# Bipolar_Matrix_Mixer_4x2.net
KiCad netlist of a schematic drawn in EAGLE
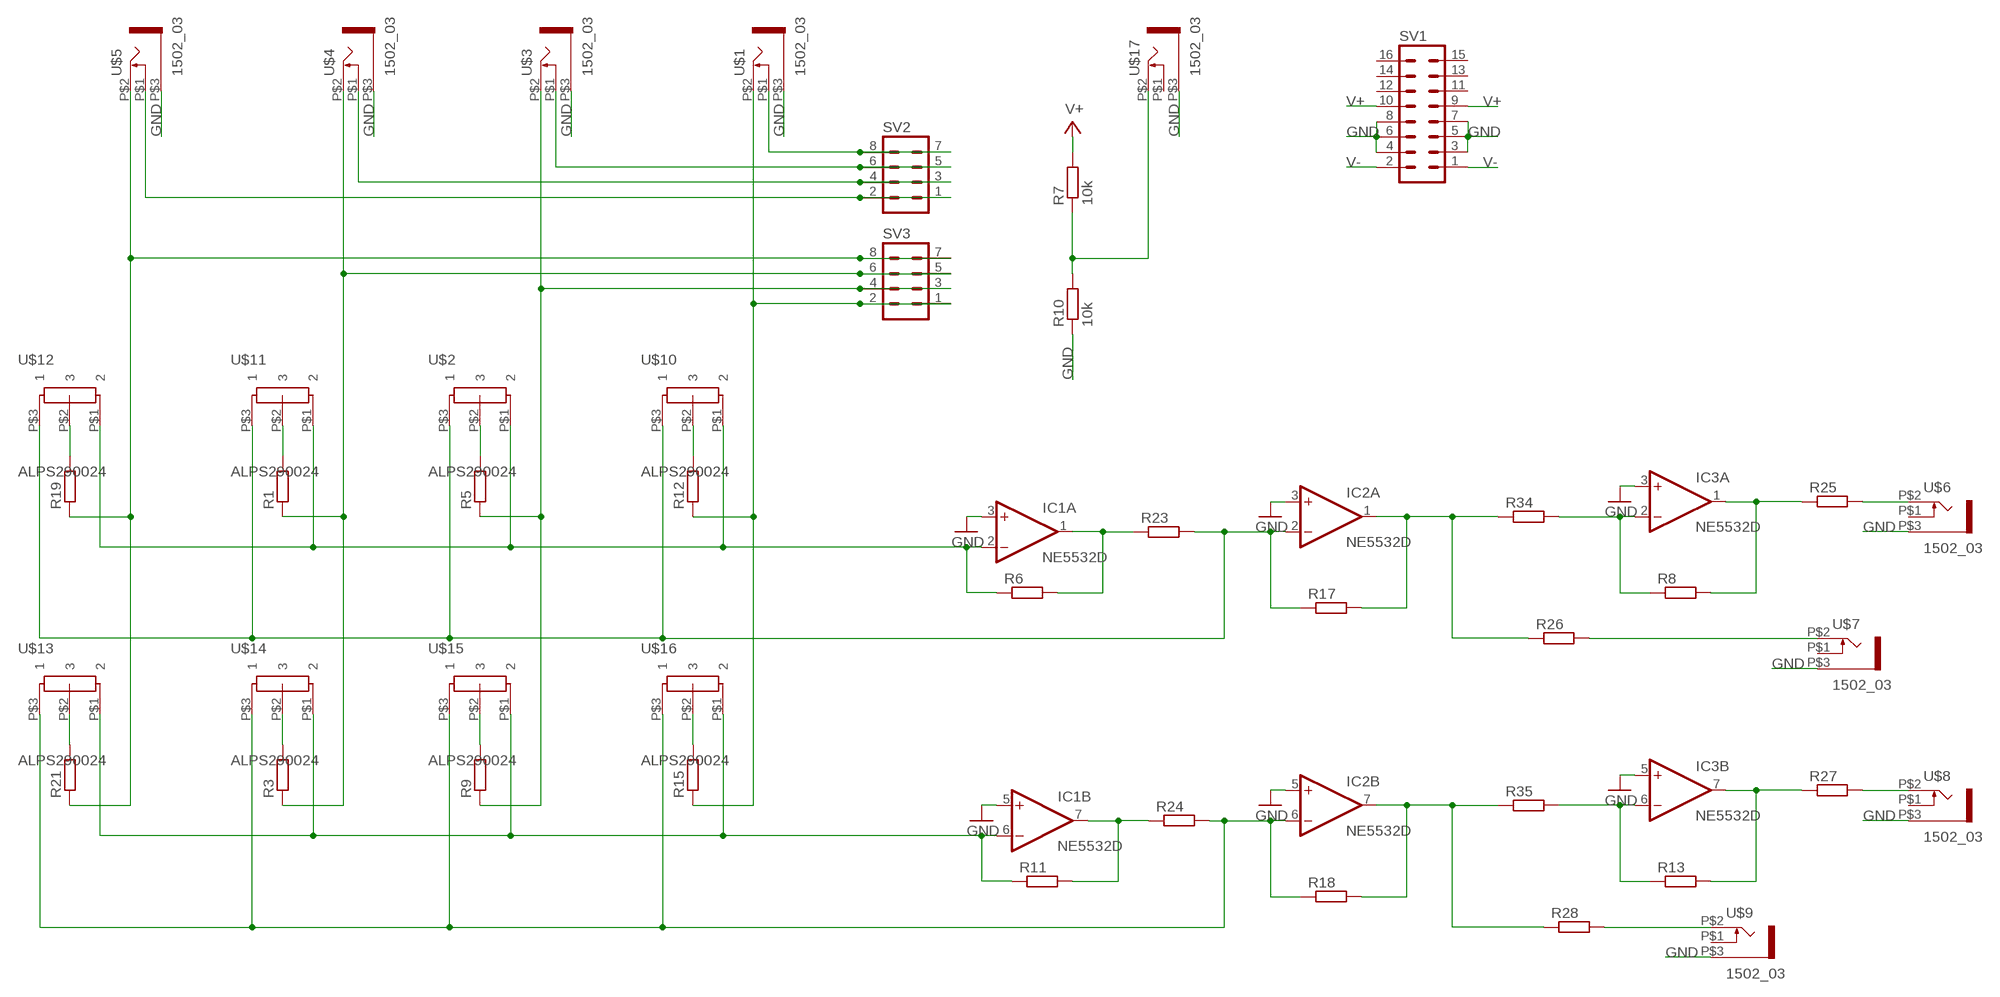
[diagram p0: schematic, sheet 1]

(export (version "E")
  (design (tool "Eeschema 10.0.6"))
  (components
    (comp (ref "IC1")
      (value "NE5532D")
      (footprint "eagle-import:SO08")
      (libsource (lib "eagle-import") (part "NE5532D"))
    )
    (comp (ref "IC2")
      (value "NE5532D")
      (footprint "eagle-import:SO08")
      (libsource (lib "eagle-import") (part "NE5532D"))
    )
    (comp (ref "IC3")
      (value "NE5532D")
      (footprint "eagle-import:SO08")
      (libsource (lib "eagle-import") (part "NE5532D"))
    )
    (comp (ref "R1")
      (value "R-EU_R0603")
      (footprint "eagle-import:R0603")
      (libsource (lib "eagle-import") (part "R-EU_R0603"))
    )
    (comp (ref "R3")
      (value "R-EU_R0603")
      (footprint "eagle-import:R0603")
      (libsource (lib "eagle-import") (part "R-EU_R0603"))
    )
    (comp (ref "R5")
      (value "R-EU_R0603")
      (footprint "eagle-import:R0603")
      (libsource (lib "eagle-import") (part "R-EU_R0603"))
    )
    (comp (ref "R6")
      (value "R-EU_R0603")
      (footprint "eagle-import:R0603")
      (libsource (lib "eagle-import") (part "R-EU_R0603"))
    )
    (comp (ref "R7")
      (value "10k")
      (footprint "eagle-import:R0603")
      (libsource (lib "eagle-import") (part "R-EU_R0603"))
    )
    (comp (ref "R8")
      (value "R-EU_R0603")
      (footprint "eagle-import:R0603")
      (libsource (lib "eagle-import") (part "R-EU_R0603"))
    )
    (comp (ref "R9")
      (value "R-EU_R0603")
      (footprint "eagle-import:R0603")
      (libsource (lib "eagle-import") (part "R-EU_R0603"))
    )
    (comp (ref "R10")
      (value "10k")
      (footprint "eagle-import:R0603")
      (libsource (lib "eagle-import") (part "R-EU_R0603"))
    )
    (comp (ref "R11")
      (value "R-EU_R0603")
      (footprint "eagle-import:R0603")
      (libsource (lib "eagle-import") (part "R-EU_R0603"))
    )
    (comp (ref "R12")
      (value "R-EU_R0603")
      (footprint "eagle-import:R0603")
      (libsource (lib "eagle-import") (part "R-EU_R0603"))
    )
    (comp (ref "R13")
      (value "R-EU_R0603")
      (footprint "eagle-import:R0603")
      (libsource (lib "eagle-import") (part "R-EU_R0603"))
    )
    (comp (ref "R15")
      (value "R-EU_R0603")
      (footprint "eagle-import:R0603")
      (libsource (lib "eagle-import") (part "R-EU_R0603"))
    )
    (comp (ref "R17")
      (value "R-EU_R0603")
      (footprint "eagle-import:R0603")
      (libsource (lib "eagle-import") (part "R-EU_R0603"))
    )
    (comp (ref "R18")
      (value "R-EU_R0603")
      (footprint "eagle-import:R0603")
      (libsource (lib "eagle-import") (part "R-EU_R0603"))
    )
    (comp (ref "R19")
      (value "R-EU_R0603")
      (footprint "eagle-import:R0603")
      (libsource (lib "eagle-import") (part "R-EU_R0603"))
    )
    (comp (ref "R21")
      (value "R-EU_R0603")
      (footprint "eagle-import:R0603")
      (libsource (lib "eagle-import") (part "R-EU_R0603"))
    )
    (comp (ref "R23")
      (value "R-EU_R0603")
      (footprint "eagle-import:R0603")
      (libsource (lib "eagle-import") (part "R-EU_R0603"))
    )
    (comp (ref "R24")
      (value "R-EU_R0603")
      (footprint "eagle-import:R0603")
      (libsource (lib "eagle-import") (part "R-EU_R0603"))
    )
    (comp (ref "R25")
      (value "R-EU_R0603")
      (footprint "eagle-import:R0603")
      (libsource (lib "eagle-import") (part "R-EU_R0603"))
    )
    (comp (ref "R26")
      (value "R-EU_R0603")
      (footprint "eagle-import:R0603")
      (libsource (lib "eagle-import") (part "R-EU_R0603"))
    )
    (comp (ref "R27")
      (value "R-EU_R0603")
      (footprint "eagle-import:R0603")
      (libsource (lib "eagle-import") (part "R-EU_R0603"))
    )
    (comp (ref "R28")
      (value "R-EU_R0603")
      (footprint "eagle-import:R0603")
      (libsource (lib "eagle-import") (part "R-EU_R0603"))
    )
    (comp (ref "R34")
      (value "R-EU_R0603")
      (footprint "eagle-import:R0603")
      (libsource (lib "eagle-import") (part "R-EU_R0603"))
    )
    (comp (ref "R35")
      (value "R-EU_R0603")
      (footprint "eagle-import:R0603")
      (libsource (lib "eagle-import") (part "R-EU_R0603"))
    )
    (comp (ref "SV1")
      (value "MA08-2")
      (footprint "eagle-import:MA08-2")
      (libsource (lib "eagle-import") (part "MA08-2"))
    )
    (comp (ref "SV2")
      (value "MA04-2")
      (footprint "eagle-import:MA04-2")
      (libsource (lib "eagle-import") (part "MA04-2"))
    )
    (comp (ref "SV3")
      (value "MA04-2")
      (footprint "eagle-import:MA04-2")
      (libsource (lib "eagle-import") (part "MA04-2"))
    )
    (comp (ref "U$1")
      (value "1502_03")
      (footprint "eagle-import:1502_03")
      (libsource (lib "eagle-import") (part "1502_03"))
    )
    (comp (ref "U$2")
      (value "ALPS290024")
      (footprint "eagle-import:POT")
      (libsource (lib "eagle-import") (part "ALPS290024"))
    )
    (comp (ref "U$3")
      (value "1502_03")
      (footprint "eagle-import:1502_03")
      (libsource (lib "eagle-import") (part "1502_03"))
    )
    (comp (ref "U$4")
      (value "1502_03")
      (footprint "eagle-import:1502_03")
      (libsource (lib "eagle-import") (part "1502_03"))
    )
    (comp (ref "U$5")
      (value "1502_03")
      (footprint "eagle-import:1502_03")
      (libsource (lib "eagle-import") (part "1502_03"))
    )
    (comp (ref "U$6")
      (value "1502_03")
      (footprint "eagle-import:1502_03")
      (libsource (lib "eagle-import") (part "1502_03"))
    )
    (comp (ref "U$7")
      (value "1502_03")
      (footprint "eagle-import:1502_03")
      (libsource (lib "eagle-import") (part "1502_03"))
    )
    (comp (ref "U$8")
      (value "1502_03")
      (footprint "eagle-import:1502_03")
      (libsource (lib "eagle-import") (part "1502_03"))
    )
    (comp (ref "U$9")
      (value "1502_03")
      (footprint "eagle-import:1502_03")
      (libsource (lib "eagle-import") (part "1502_03"))
    )
    (comp (ref "U$10")
      (value "ALPS290024")
      (footprint "eagle-import:POT")
      (libsource (lib "eagle-import") (part "ALPS290024"))
    )
    (comp (ref "U$11")
      (value "ALPS290024")
      (footprint "eagle-import:POT")
      (libsource (lib "eagle-import") (part "ALPS290024"))
    )
    (comp (ref "U$12")
      (value "ALPS290024")
      (footprint "eagle-import:POT")
      (libsource (lib "eagle-import") (part "ALPS290024"))
    )
    (comp (ref "U$13")
      (value "ALPS290024")
      (footprint "eagle-import:POT")
      (libsource (lib "eagle-import") (part "ALPS290024"))
    )
    (comp (ref "U$14")
      (value "ALPS290024")
      (footprint "eagle-import:POT")
      (libsource (lib "eagle-import") (part "ALPS290024"))
    )
    (comp (ref "U$15")
      (value "ALPS290024")
      (footprint "eagle-import:POT")
      (libsource (lib "eagle-import") (part "ALPS290024"))
    )
    (comp (ref "U$16")
      (value "ALPS290024")
      (footprint "eagle-import:POT")
      (libsource (lib "eagle-import") (part "ALPS290024"))
    )
    (comp (ref "U$17")
      (value "1502_03")
      (footprint "eagle-import:1502_03")
      (libsource (lib "eagle-import") (part "1502_03"))
    )
  )
  (nets
    (net (code "1") (name "/V-") (class "Default")
      (node (ref "SV1") (pin "1") (pinfunction "1_1") (pintype "passive"))
      (node (ref "SV1") (pin "2") (pinfunction "2_2") (pintype "passive"))
    )
    (net (code "2") (name "GND") (class "Default")
      (node (ref "IC1") (pin "3") (pinfunction "+IN_3") (pintype "input"))
      (node (ref "IC1") (pin "5") (pinfunction "+IN_5") (pintype "input"))
      (node (ref "IC2") (pin "3") (pinfunction "+IN_3") (pintype "input"))
      (node (ref "IC2") (pin "5") (pinfunction "+IN_5") (pintype "input"))
      (node (ref "IC3") (pin "3") (pinfunction "+IN_3") (pintype "input"))
      (node (ref "IC3") (pin "5") (pinfunction "+IN_5") (pintype "input"))
      (node (ref "R10") (pin "1") (pinfunction "1_1") (pintype "passive"))
      (node (ref "SV1") (pin "3") (pinfunction "3_3") (pintype "passive"))
      (node (ref "SV1") (pin "4") (pinfunction "4_4") (pintype "passive"))
      (node (ref "SV1") (pin "5") (pinfunction "5_5") (pintype "passive"))
      (node (ref "SV1") (pin "6") (pinfunction "6_6") (pintype "passive"))
      (node (ref "SV1") (pin "7") (pinfunction "7_7") (pintype "passive"))
      (node (ref "SV1") (pin "8") (pinfunction "8_8") (pintype "passive"))
      (node (ref "U$1") (pin "P$3") (pinfunction "5_P$3") (pintype "passive"))
      (node (ref "U$17") (pin "P$3") (pinfunction "5_P$3") (pintype "passive"))
      (node (ref "U$3") (pin "P$3") (pinfunction "5_P$3") (pintype "passive"))
      (node (ref "U$4") (pin "P$3") (pinfunction "5_P$3") (pintype "passive"))
      (node (ref "U$5") (pin "P$3") (pinfunction "5_P$3") (pintype "passive"))
      (node (ref "U$6") (pin "P$3") (pinfunction "5_P$3") (pintype "passive"))
      (node (ref "U$7") (pin "P$3") (pinfunction "5_P$3") (pintype "passive"))
      (node (ref "U$8") (pin "P$3") (pinfunction "5_P$3") (pintype "passive"))
      (node (ref "U$9") (pin "P$3") (pinfunction "5_P$3") (pintype "passive"))
    )
    (net (code "3") (name "Net-(IC1A--IN)") (class "Default")
      (node (ref "IC1") (pin "2") (pinfunction "-IN_2") (pintype "input"))
      (node (ref "R6") (pin "1") (pinfunction "1_1") (pintype "passive"))
      (node (ref "U$10") (pin "P$1") (pinfunction "2_P$1") (pintype "bidirectional"))
      (node (ref "U$11") (pin "P$1") (pinfunction "2_P$1") (pintype "bidirectional"))
      (node (ref "U$12") (pin "P$1") (pinfunction "2_P$1") (pintype "bidirectional"))
      (node (ref "U$2") (pin "P$1") (pinfunction "2_P$1") (pintype "bidirectional"))
    )
    (net (code "4") (name "Net-(IC1A-OUT)") (class "Default")
      (node (ref "IC1") (pin "1") (pinfunction "OUT_1") (pintype "output"))
      (node (ref "R23") (pin "1") (pinfunction "1_1") (pintype "passive"))
      (node (ref "R6") (pin "2") (pinfunction "2_2") (pintype "passive"))
    )
    (net (code "5") (name "Net-(IC1B--IN)") (class "Default")
      (node (ref "IC1") (pin "6") (pinfunction "-IN_6") (pintype "input"))
      (node (ref "R11") (pin "1") (pinfunction "1_1") (pintype "passive"))
      (node (ref "U$13") (pin "P$1") (pinfunction "2_P$1") (pintype "bidirectional"))
      (node (ref "U$14") (pin "P$1") (pinfunction "2_P$1") (pintype "bidirectional"))
      (node (ref "U$15") (pin "P$1") (pinfunction "2_P$1") (pintype "bidirectional"))
      (node (ref "U$16") (pin "P$1") (pinfunction "2_P$1") (pintype "bidirectional"))
    )
    (net (code "6") (name "Net-(IC1B-OUT)") (class "Default")
      (node (ref "IC1") (pin "7") (pinfunction "OUT_7") (pintype "output"))
      (node (ref "R11") (pin "2") (pinfunction "2_2") (pintype "passive"))
      (node (ref "R24") (pin "1") (pinfunction "1_1") (pintype "passive"))
    )
    (net (code "7") (name "Net-(IC2A--IN)") (class "Default")
      (node (ref "IC2") (pin "2") (pinfunction "-IN_2") (pintype "input"))
      (node (ref "R17") (pin "1") (pinfunction "1_1") (pintype "passive"))
      (node (ref "R23") (pin "2") (pinfunction "2_2") (pintype "passive"))
      (node (ref "U$10") (pin "P$3") (pinfunction "1_P$3") (pintype "bidirectional"))
      (node (ref "U$11") (pin "P$3") (pinfunction "1_P$3") (pintype "bidirectional"))
      (node (ref "U$12") (pin "P$3") (pinfunction "1_P$3") (pintype "bidirectional"))
      (node (ref "U$2") (pin "P$3") (pinfunction "1_P$3") (pintype "bidirectional"))
    )
    (net (code "8") (name "Net-(IC2A-OUT)") (class "Default")
      (node (ref "IC2") (pin "1") (pinfunction "OUT_1") (pintype "output"))
      (node (ref "R17") (pin "2") (pinfunction "2_2") (pintype "passive"))
      (node (ref "R26") (pin "1") (pinfunction "1_1") (pintype "passive"))
      (node (ref "R34") (pin "1") (pinfunction "1_1") (pintype "passive"))
    )
    (net (code "9") (name "Net-(IC2B--IN)") (class "Default")
      (node (ref "IC2") (pin "6") (pinfunction "-IN_6") (pintype "input"))
      (node (ref "R18") (pin "1") (pinfunction "1_1") (pintype "passive"))
      (node (ref "R24") (pin "2") (pinfunction "2_2") (pintype "passive"))
      (node (ref "U$13") (pin "P$3") (pinfunction "1_P$3") (pintype "bidirectional"))
      (node (ref "U$14") (pin "P$3") (pinfunction "1_P$3") (pintype "bidirectional"))
      (node (ref "U$15") (pin "P$3") (pinfunction "1_P$3") (pintype "bidirectional"))
      (node (ref "U$16") (pin "P$3") (pinfunction "1_P$3") (pintype "bidirectional"))
    )
    (net (code "10") (name "Net-(IC2B-OUT)") (class "Default")
      (node (ref "IC2") (pin "7") (pinfunction "OUT_7") (pintype "output"))
      (node (ref "R18") (pin "2") (pinfunction "2_2") (pintype "passive"))
      (node (ref "R28") (pin "1") (pinfunction "1_1") (pintype "passive"))
      (node (ref "R35") (pin "1") (pinfunction "1_1") (pintype "passive"))
    )
    (net (code "11") (name "Net-(IC3A--IN)") (class "Default")
      (node (ref "IC3") (pin "2") (pinfunction "-IN_2") (pintype "input"))
      (node (ref "R34") (pin "2") (pinfunction "2_2") (pintype "passive"))
      (node (ref "R8") (pin "1") (pinfunction "1_1") (pintype "passive"))
    )
    (net (code "12") (name "Net-(IC3A-OUT)") (class "Default")
      (node (ref "IC3") (pin "1") (pinfunction "OUT_1") (pintype "output"))
      (node (ref "R25") (pin "1") (pinfunction "1_1") (pintype "passive"))
      (node (ref "R8") (pin "2") (pinfunction "2_2") (pintype "passive"))
    )
    (net (code "13") (name "Net-(IC3B--IN)") (class "Default")
      (node (ref "IC3") (pin "6") (pinfunction "-IN_6") (pintype "input"))
      (node (ref "R13") (pin "1") (pinfunction "1_1") (pintype "passive"))
      (node (ref "R35") (pin "2") (pinfunction "2_2") (pintype "passive"))
    )
    (net (code "14") (name "Net-(IC3B-OUT)") (class "Default")
      (node (ref "IC3") (pin "7") (pinfunction "OUT_7") (pintype "output"))
      (node (ref "R13") (pin "2") (pinfunction "2_2") (pintype "passive"))
      (node (ref "R27") (pin "1") (pinfunction "1_1") (pintype "passive"))
    )
    (net (code "15") (name "Net-(U$1-3)") (class "Default")
      (node (ref "R12") (pin "1") (pinfunction "1_1") (pintype "passive"))
      (node (ref "R15") (pin "1") (pinfunction "1_1") (pintype "passive"))
      (node (ref "SV3") (pin "1") (pinfunction "1_1") (pintype "passive"))
      (node (ref "SV3") (pin "2") (pinfunction "2_2") (pintype "passive"))
      (node (ref "U$1") (pin "P$2") (pinfunction "3_P$2") (pintype "passive"))
    )
    (net (code "16") (name "Net-(U$1-4)") (class "Default")
      (node (ref "SV2") (pin "7") (pinfunction "7_7") (pintype "passive"))
      (node (ref "SV2") (pin "8") (pinfunction "8_8") (pintype "passive"))
      (node (ref "U$1") (pin "P$1") (pinfunction "4_P$1") (pintype "passive"))
    )
    (net (code "17") (name "Net-(U$2-3)") (class "Default")
      (node (ref "R5") (pin "2") (pinfunction "2_2") (pintype "passive"))
      (node (ref "U$2") (pin "P$2") (pinfunction "3_P$2") (pintype "bidirectional"))
    )
    (net (code "18") (name "Net-(U$3-3)") (class "Default")
      (node (ref "R5") (pin "1") (pinfunction "1_1") (pintype "passive"))
      (node (ref "R9") (pin "1") (pinfunction "1_1") (pintype "passive"))
      (node (ref "SV3") (pin "3") (pinfunction "3_3") (pintype "passive"))
      (node (ref "SV3") (pin "4") (pinfunction "4_4") (pintype "passive"))
      (node (ref "U$3") (pin "P$2") (pinfunction "3_P$2") (pintype "passive"))
    )
    (net (code "19") (name "Net-(U$3-4)") (class "Default")
      (node (ref "SV2") (pin "5") (pinfunction "5_5") (pintype "passive"))
      (node (ref "SV2") (pin "6") (pinfunction "6_6") (pintype "passive"))
      (node (ref "U$3") (pin "P$1") (pinfunction "4_P$1") (pintype "passive"))
    )
    (net (code "20") (name "Net-(U$4-3)") (class "Default")
      (node (ref "R1") (pin "1") (pinfunction "1_1") (pintype "passive"))
      (node (ref "R3") (pin "1") (pinfunction "1_1") (pintype "passive"))
      (node (ref "SV3") (pin "5") (pinfunction "5_5") (pintype "passive"))
      (node (ref "SV3") (pin "6") (pinfunction "6_6") (pintype "passive"))
      (node (ref "U$4") (pin "P$2") (pinfunction "3_P$2") (pintype "passive"))
    )
    (net (code "21") (name "Net-(U$4-4)") (class "Default")
      (node (ref "SV2") (pin "3") (pinfunction "3_3") (pintype "passive"))
      (node (ref "SV2") (pin "4") (pinfunction "4_4") (pintype "passive"))
      (node (ref "U$4") (pin "P$1") (pinfunction "4_P$1") (pintype "passive"))
    )
    (net (code "22") (name "Net-(U$5-3)") (class "Default")
      (node (ref "R19") (pin "1") (pinfunction "1_1") (pintype "passive"))
      (node (ref "R21") (pin "1") (pinfunction "1_1") (pintype "passive"))
      (node (ref "SV3") (pin "7") (pinfunction "7_7") (pintype "passive"))
      (node (ref "SV3") (pin "8") (pinfunction "8_8") (pintype "passive"))
      (node (ref "U$5") (pin "P$2") (pinfunction "3_P$2") (pintype "passive"))
    )
    (net (code "23") (name "Net-(U$5-4)") (class "Default")
      (node (ref "SV2") (pin "1") (pinfunction "1_1") (pintype "passive"))
      (node (ref "SV2") (pin "2") (pinfunction "2_2") (pintype "passive"))
      (node (ref "U$5") (pin "P$1") (pinfunction "4_P$1") (pintype "passive"))
    )
    (net (code "24") (name "Net-(U$6-3)") (class "Default")
      (node (ref "R25") (pin "2") (pinfunction "2_2") (pintype "passive"))
      (node (ref "U$6") (pin "P$2") (pinfunction "3_P$2") (pintype "passive"))
    )
    (net (code "25") (name "Net-(U$7-3)") (class "Default")
      (node (ref "R26") (pin "2") (pinfunction "2_2") (pintype "passive"))
      (node (ref "U$7") (pin "P$2") (pinfunction "3_P$2") (pintype "passive"))
    )
    (net (code "26") (name "Net-(U$8-3)") (class "Default")
      (node (ref "R27") (pin "2") (pinfunction "2_2") (pintype "passive"))
      (node (ref "U$8") (pin "P$2") (pinfunction "3_P$2") (pintype "passive"))
    )
    (net (code "27") (name "Net-(U$9-3)") (class "Default")
      (node (ref "R28") (pin "2") (pinfunction "2_2") (pintype "passive"))
      (node (ref "U$9") (pin "P$2") (pinfunction "3_P$2") (pintype "passive"))
    )
    (net (code "28") (name "Net-(U$10-3)") (class "Default")
      (node (ref "R12") (pin "2") (pinfunction "2_2") (pintype "passive"))
      (node (ref "U$10") (pin "P$2") (pinfunction "3_P$2") (pintype "bidirectional"))
    )
    (net (code "29") (name "Net-(U$11-3)") (class "Default")
      (node (ref "R1") (pin "2") (pinfunction "2_2") (pintype "passive"))
      (node (ref "U$11") (pin "P$2") (pinfunction "3_P$2") (pintype "bidirectional"))
    )
    (net (code "30") (name "Net-(U$12-3)") (class "Default")
      (node (ref "R19") (pin "2") (pinfunction "2_2") (pintype "passive"))
      (node (ref "U$12") (pin "P$2") (pinfunction "3_P$2") (pintype "bidirectional"))
    )
    (net (code "31") (name "Net-(U$13-3)") (class "Default")
      (node (ref "R21") (pin "2") (pinfunction "2_2") (pintype "passive"))
      (node (ref "U$13") (pin "P$2") (pinfunction "3_P$2") (pintype "bidirectional"))
    )
    (net (code "32") (name "Net-(U$14-3)") (class "Default")
      (node (ref "R3") (pin "2") (pinfunction "2_2") (pintype "passive"))
      (node (ref "U$14") (pin "P$2") (pinfunction "3_P$2") (pintype "bidirectional"))
    )
    (net (code "33") (name "Net-(U$15-3)") (class "Default")
      (node (ref "R9") (pin "2") (pinfunction "2_2") (pintype "passive"))
      (node (ref "U$15") (pin "P$2") (pinfunction "3_P$2") (pintype "bidirectional"))
    )
    (net (code "34") (name "Net-(U$16-3)") (class "Default")
      (node (ref "R15") (pin "2") (pinfunction "2_2") (pintype "passive"))
      (node (ref "U$16") (pin "P$2") (pinfunction "3_P$2") (pintype "bidirectional"))
    )
    (net (code "35") (name "Net-(U$17-3)") (class "Default")
      (node (ref "R10") (pin "2") (pinfunction "2_2") (pintype "passive"))
      (node (ref "R7") (pin "1") (pinfunction "1_1") (pintype "passive"))
      (node (ref "U$17") (pin "P$2") (pinfunction "3_P$2") (pintype "passive"))
    )
    (net (code "36") (name "V+") (class "Default")
      (node (ref "R7") (pin "2") (pinfunction "2_2") (pintype "passive"))
      (node (ref "SV1") (pin "10") (pinfunction "10_10") (pintype "passive"))
      (node (ref "SV1") (pin "9") (pinfunction "9_9") (pintype "passive"))
    )
    (net (code "37") (name "unconnected-(SV1-Pad11)") (class "Default")
      (node (ref "SV1") (pin "11") (pinfunction "11_11") (pintype "passive"))
    )
    (net (code "38") (name "unconnected-(SV1-Pad12)") (class "Default")
      (node (ref "SV1") (pin "12") (pinfunction "12_12") (pintype "passive"))
    )
    (net (code "39") (name "unconnected-(SV1-Pad13)") (class "Default")
      (node (ref "SV1") (pin "13") (pinfunction "13_13") (pintype "passive"))
    )
    (net (code "40") (name "unconnected-(SV1-Pad14)") (class "Default")
      (node (ref "SV1") (pin "14") (pinfunction "14_14") (pintype "passive"))
    )
    (net (code "41") (name "unconnected-(SV1-Pad15)") (class "Default")
      (node (ref "SV1") (pin "15") (pinfunction "15_15") (pintype "passive"))
    )
    (net (code "42") (name "unconnected-(SV1-Pad16)") (class "Default")
      (node (ref "SV1") (pin "16") (pinfunction "16_16") (pintype "passive"))
    )
    (net (code "43") (name "unconnected-(U$6-4-PadP$1)") (class "Default")
      (node (ref "U$6") (pin "P$1") (pinfunction "4_P$1") (pintype "passive"))
    )
    (net (code "44") (name "unconnected-(U$7-4-PadP$1)") (class "Default")
      (node (ref "U$7") (pin "P$1") (pinfunction "4_P$1") (pintype "passive"))
    )
    (net (code "45") (name "unconnected-(U$8-4-PadP$1)") (class "Default")
      (node (ref "U$8") (pin "P$1") (pinfunction "4_P$1") (pintype "passive"))
    )
    (net (code "46") (name "unconnected-(U$9-4-PadP$1)") (class "Default")
      (node (ref "U$9") (pin "P$1") (pinfunction "4_P$1") (pintype "passive"))
    )
    (net (code "47") (name "unconnected-(U$17-4-PadP$1)") (class "Default")
      (node (ref "U$17") (pin "P$1") (pinfunction "4_P$1") (pintype "passive"))
    )
  )
)
